# HUB_Sheet3.net
KiCad netlist of a schematic drawn in Altium Designer
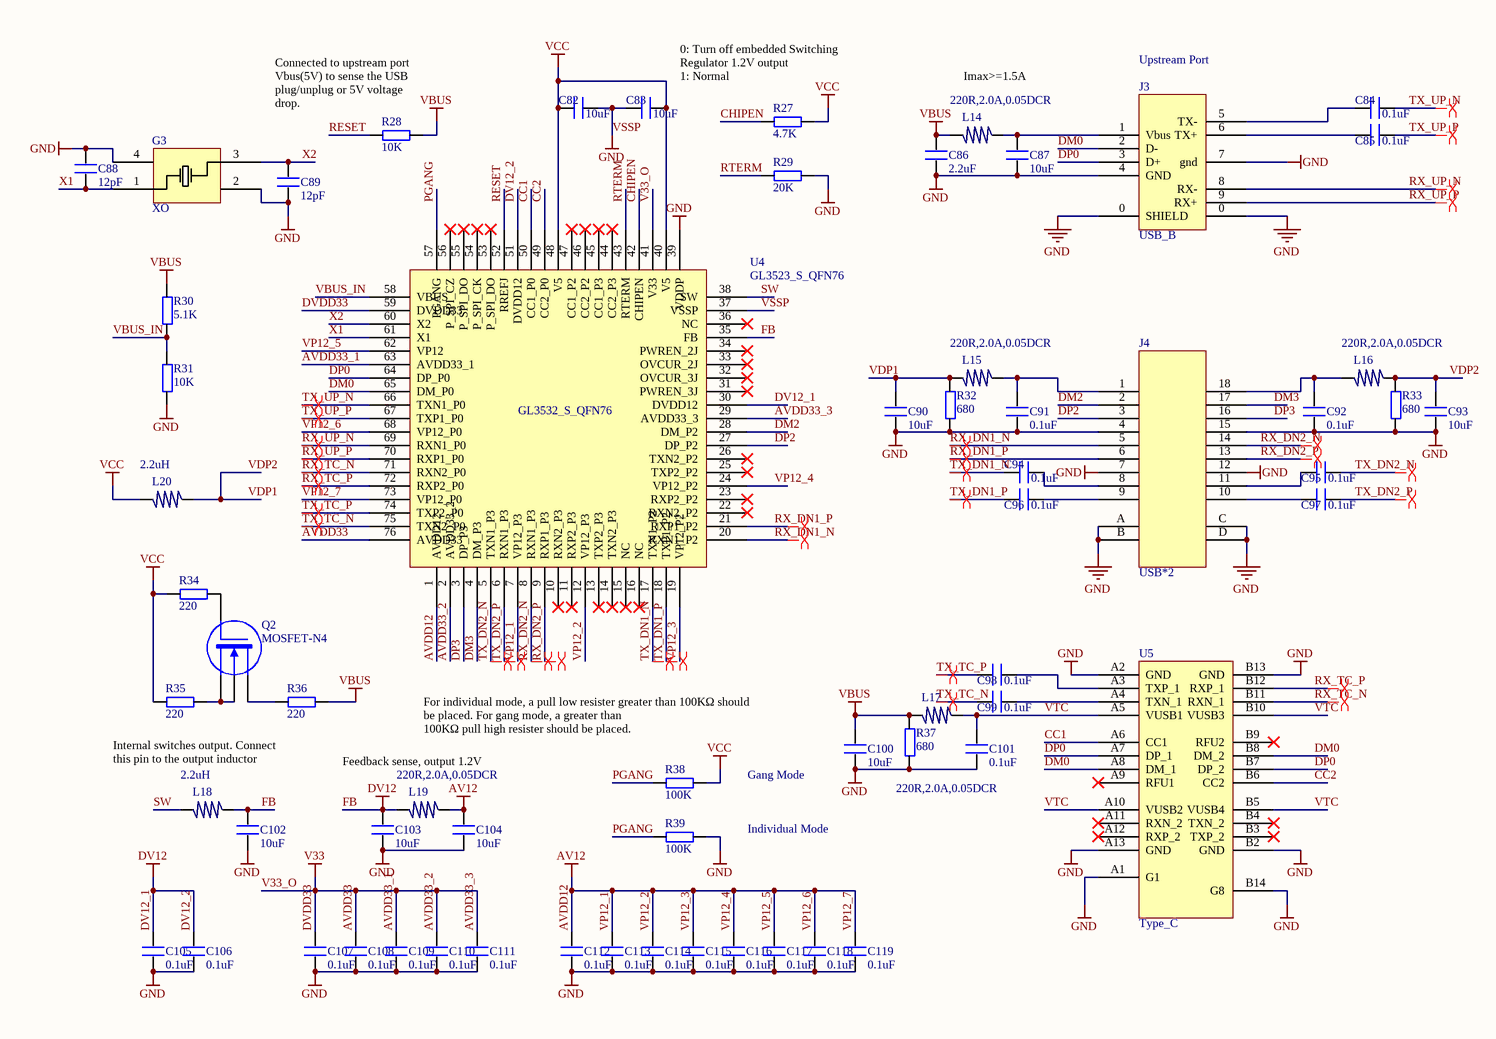
[diagram p0: HUB_Sheet3.SchDoc]

(export (version "E")
  (design (tool "Eeschema 10.0.6"))
  (components
    (comp (ref "C82") (value "10uF") (footprint "0603P") (libsource (lib "Explorer STM32F407封装库") (part "C")))
    (comp (ref "C83") (value "10uF") (footprint "0603P") (libsource (lib "Explorer STM32F407封装库") (part "C")))
    (comp (ref "C84")
      (value "0.1uF")
      (footprint "0603P")
      (libsource (lib "Explorer STM32F407封装库") (part "C"))
    )
    (comp (ref "C85")
      (value "0.1uF")
      (footprint "0603P")
      (libsource (lib "Explorer STM32F407封装库") (part "C"))
    )
    (comp (ref "C86")
      (value "2.2uF")
      (footprint "0603P")
      (libsource (lib "Explorer STM32F407封装库") (part "C"))
    )
    (comp (ref "C87") (value "10uF") (footprint "0603P") (libsource (lib "Explorer STM32F407封装库") (part "C")))
    (comp (ref "C88") (value "12pF") (footprint "0603P") (libsource (lib "Explorer STM32F407封装库") (part "C")))
    (comp (ref "C89") (value "12pF") (footprint "0603P") (libsource (lib "Explorer STM32F407封装库") (part "C")))
    (comp (ref "C90") (value "10uF") (footprint "0603P") (libsource (lib "Explorer STM32F407封装库") (part "C")))
    (comp (ref "C91")
      (value "0.1uF")
      (footprint "0603P")
      (libsource (lib "Explorer STM32F407封装库") (part "C"))
    )
    (comp (ref "C92")
      (value "0.1uF")
      (footprint "0603P")
      (libsource (lib "Explorer STM32F407封装库") (part "C"))
    )
    (comp (ref "C93") (value "10uF") (footprint "0603P") (libsource (lib "Explorer STM32F407封装库") (part "C")))
    (comp (ref "C94")
      (value "0.1uF")
      (footprint "0603P")
      (libsource (lib "Explorer STM32F407封装库") (part "C"))
    )
    (comp (ref "C95")
      (value "0.1uF")
      (footprint "0603P")
      (libsource (lib "Explorer STM32F407封装库") (part "C"))
    )
    (comp (ref "C96")
      (value "0.1uF")
      (footprint "0603P")
      (libsource (lib "Explorer STM32F407封装库") (part "C"))
    )
    (comp (ref "C97")
      (value "0.1uF")
      (footprint "0603P")
      (libsource (lib "Explorer STM32F407封装库") (part "C"))
    )
    (comp (ref "C98")
      (value "0.1uF")
      (footprint "0603P")
      (libsource (lib "Explorer STM32F407封装库") (part "C"))
    )
    (comp (ref "C99")
      (value "0.1uF")
      (footprint "0603P")
      (libsource (lib "Explorer STM32F407封装库") (part "C"))
    )
    (comp (ref "C100")
      (value "10uF")
      (footprint "0603P")
      (libsource (lib "Explorer STM32F407封装库") (part "C"))
    )
    (comp (ref "C101")
      (value "0.1uF")
      (footprint "0603P")
      (libsource (lib "Explorer STM32F407封装库") (part "C"))
    )
    (comp (ref "C102")
      (value "10uF")
      (footprint "0603P")
      (libsource (lib "Explorer STM32F407封装库") (part "C"))
    )
    (comp (ref "C103")
      (value "10uF")
      (footprint "0603P")
      (libsource (lib "Explorer STM32F407封装库") (part "C"))
    )
    (comp (ref "C104")
      (value "10uF")
      (footprint "0603P")
      (libsource (lib "Explorer STM32F407封装库") (part "C"))
    )
    (comp (ref "C105")
      (value "0.1uF")
      (footprint "0603P")
      (libsource (lib "Explorer STM32F407封装库") (part "C"))
    )
    (comp (ref "C106")
      (value "0.1uF")
      (footprint "0603P")
      (libsource (lib "Explorer STM32F407封装库") (part "C"))
    )
    (comp (ref "C107")
      (value "0.1uF")
      (footprint "0603P")
      (libsource (lib "Explorer STM32F407封装库") (part "C"))
    )
    (comp (ref "C108")
      (value "0.1uF")
      (footprint "0603P")
      (libsource (lib "Explorer STM32F407封装库") (part "C"))
    )
    (comp (ref "C109")
      (value "0.1uF")
      (footprint "0603P")
      (libsource (lib "Explorer STM32F407封装库") (part "C"))
    )
    (comp (ref "C110")
      (value "0.1uF")
      (footprint "0603P")
      (libsource (lib "Explorer STM32F407封装库") (part "C"))
    )
    (comp (ref "C111")
      (value "0.1uF")
      (footprint "0603P")
      (libsource (lib "Explorer STM32F407封装库") (part "C"))
    )
    (comp (ref "C112")
      (value "0.1uF")
      (footprint "0603P")
      (libsource (lib "Explorer STM32F407封装库") (part "C"))
    )
    (comp (ref "C113")
      (value "0.1uF")
      (footprint "0603P")
      (libsource (lib "Explorer STM32F407封装库") (part "C"))
    )
    (comp (ref "C114")
      (value "0.1uF")
      (footprint "0603P")
      (libsource (lib "Explorer STM32F407封装库") (part "C"))
    )
    (comp (ref "C115")
      (value "0.1uF")
      (footprint "0603P")
      (libsource (lib "Explorer STM32F407封装库") (part "C"))
    )
    (comp (ref "C116")
      (value "0.1uF")
      (footprint "0603P")
      (libsource (lib "Explorer STM32F407封装库") (part "C"))
    )
    (comp (ref "C117")
      (value "0.1uF")
      (footprint "0603P")
      (libsource (lib "Explorer STM32F407封装库") (part "C"))
    )
    (comp (ref "C118")
      (value "0.1uF")
      (footprint "0603P")
      (libsource (lib "Explorer STM32F407封装库") (part "C"))
    )
    (comp (ref "C119")
      (value "0.1uF")
      (footprint "0603P")
      (libsource (lib "Explorer STM32F407封装库") (part "C"))
    )
    (comp (ref "G3")
      (value "XO")
      (footprint "XTAL")
      (description "25M XO")
      (libsource (lib "HUB_GL3532") (part "XO"))
    )
    (comp (ref "J3")
      (value "USB_B")
      (footprint "USB3.0_TP")
      (description "USB3.0_B")
      (libsource (lib "HUB_GL3532") (part "USB_B"))
    )
    (comp (ref "J4")
      (value "USB*2")
      (footprint "USB3.0_Double_DIP")
      (libsource (lib "HUB_GL3532") (part "USB*2"))
    )
    (comp (ref "L14")
      (value "220R,2.0A,0.05DCR")
      (footprint "0603P")
      (libsource (lib "Explorer STM32F407封装库") (part "L"))
    )
    (comp (ref "L15")
      (value "220R,2.0A,0.05DCR")
      (footprint "0603P")
      (libsource (lib "Explorer STM32F407封装库") (part "L"))
    )
    (comp (ref "L16")
      (value "220R,2.0A,0.05DCR")
      (footprint "0603P")
      (libsource (lib "Explorer STM32F407封装库") (part "L"))
    )
    (comp (ref "L17")
      (value "220R,2.0A,0.05DCR")
      (footprint "0603P")
      (libsource (lib "Explorer STM32F407封装库") (part "L"))
    )
    (comp (ref "L18")
      (value "2.2uH")
      (footprint "0603P")
      (libsource (lib "Explorer STM32F407封装库") (part "L"))
    )
    (comp (ref "L19")
      (value "220R,2.0A,0.05DCR")
      (footprint "0603P")
      (libsource (lib "Explorer STM32F407封装库") (part "L"))
    )
    (comp (ref "L20")
      (value "2.2uH")
      (footprint "0603P")
      (libsource (lib "Explorer STM32F407封装库") (part "L"))
    )
    (comp (ref "Q2")
      (value "MOSFET-N4")
      (footprint "SOT-343_N")
      (description "N-Channel MOSFET, Externally Terminated Substrate")
      (fields (field (name "PUBLISHER") "Altium Limited"))
      (libsource (lib "Miscellaneous Devices") (part "MOSFET-N4"))
    )
    (comp (ref "R27") (value "4.7K") (footprint "0603P") (libsource (lib "Explorer STM32F407封装库") (part "R")))
    (comp (ref "R28") (value "10K") (footprint "0603P") (libsource (lib "Explorer STM32F407封装库") (part "R")))
    (comp (ref "R29") (value "20K") (footprint "0603P") (libsource (lib "Explorer STM32F407封装库") (part "R")))
    (comp (ref "R30") (value "5.1K") (footprint "0603P") (libsource (lib "Explorer STM32F407封装库") (part "R")))
    (comp (ref "R31") (value "10K") (footprint "0603P") (libsource (lib "Explorer STM32F407封装库") (part "R")))
    (comp (ref "R32") (value "680") (footprint "0603P") (libsource (lib "Explorer STM32F407封装库") (part "R")))
    (comp (ref "R33") (value "680") (footprint "0603P") (libsource (lib "Explorer STM32F407封装库") (part "R")))
    (comp (ref "R34") (value "220") (footprint "0603P") (libsource (lib "Explorer STM32F407封装库") (part "R")))
    (comp (ref "R35") (value "220") (footprint "0603P") (libsource (lib "Explorer STM32F407封装库") (part "R")))
    (comp (ref "R36") (value "220") (footprint "0603P") (libsource (lib "Explorer STM32F407封装库") (part "R")))
    (comp (ref "R37") (value "680") (footprint "0603P") (libsource (lib "Explorer STM32F407封装库") (part "R")))
    (comp (ref "R38") (value "100K") (footprint "0603P") (libsource (lib "Explorer STM32F407封装库") (part "R")))
    (comp (ref "R39") (value "100K") (footprint "0603P") (libsource (lib "Explorer STM32F407封装库") (part "R")))
    (comp (ref "U4")
      (value "GL3523_S_QFN76")
      (footprint "GL3523_QFN76")
      (libsource (lib "HUB_GL3532") (part "GL3523_S_QFN76"))
    )
    (comp (ref "U5") (value "Type_C") (libsource (lib "HUB_GL3532") (part "Type_C")))
  )
  (nets
    (net (code "1") (name "/CC1") (class "Default")
      (node (ref "U4") (pin "50") (pinfunction "CC1_P0_50") (pintype "passive"))
      (node (ref "U5") (pin "A6") (pinfunction "CC1_A6") (pintype "passive"))
    )
    (net (code "2") (name "/CC2") (class "Default")
      (node (ref "U4") (pin "49") (pinfunction "CC2_P0_49") (pintype "passive"))
      (node (ref "U5") (pin "B6") (pinfunction "CC2_B6") (pintype "passive"))
    )
    (net (code "3") (name "/CHIPEN") (class "Default")
      (node (ref "R27") (pin "1") (pintype "passive"))
      (node (ref "U4") (pin "42") (pinfunction "CHIPEN_42") (pintype "passive"))
    )
    (net (code "4") (name "/DM0") (class "Default")
      (node (ref "J3") (pin "2") (pinfunction "D-_2") (pintype "passive"))
      (node (ref "U4") (pin "65") (pinfunction "DM_P0_65") (pintype "passive"))
      (node (ref "U5") (pin "A8") (pinfunction "DM_1_A8") (pintype "passive"))
      (node (ref "U5") (pin "B8") (pinfunction "DM_2_B8") (pintype "passive"))
    )
    (net (code "5") (name "/DM2") (class "Default")
      (node (ref "J4") (pin "2") (pintype "passive"))
      (node (ref "U4") (pin "28") (pinfunction "DM_P2_28") (pintype "passive"))
    )
    (net (code "6") (name "/DM3") (class "Default")
      (node (ref "J4") (pin "17") (pintype "passive"))
      (node (ref "U4") (pin "4") (pinfunction "DM_P3_4") (pintype "passive"))
    )
    (net (code "7") (name "/DP0") (class "Default")
      (node (ref "J3") (pin "3") (pinfunction "D+_3") (pintype "passive"))
      (node (ref "U4") (pin "64") (pinfunction "DP_P0_64") (pintype "passive"))
      (node (ref "U5") (pin "A7") (pinfunction "DP_1_A7") (pintype "passive"))
      (node (ref "U5") (pin "B7") (pinfunction "DP_2_B7") (pintype "passive"))
    )
    (net (code "8") (name "/DP2") (class "Default")
      (node (ref "J4") (pin "3") (pintype "passive"))
      (node (ref "U4") (pin "27") (pinfunction "DP_P2_27") (pintype "passive"))
    )
    (net (code "9") (name "/DP3") (class "Default")
      (node (ref "J4") (pin "16") (pintype "passive"))
      (node (ref "U4") (pin "3") (pinfunction "DP_P3_3") (pintype "passive"))
    )
    (net (code "10") (name "/PGANG") (class "Default")
      (node (ref "R38") (pin "1") (pintype "passive"))
      (node (ref "R39") (pin "1") (pintype "passive"))
      (node (ref "U4") (pin "57") (pinfunction "PGANG_57") (pintype "passive"))
    )
    (net (code "11") (name "/RESET") (class "Default")
      (node (ref "R28") (pin "1") (pintype "passive"))
      (node (ref "U4") (pin "52") (pinfunction "RREFJ_52") (pintype "passive"))
    )
    (net (code "12") (name "/RTERM") (class "Default")
      (node (ref "R29") (pin "1") (pintype "passive"))
      (node (ref "U4") (pin "43") (pinfunction "RTERM_43") (pintype "passive"))
    )
    (net (code "13") (name "/RX_DN1_N") (class "Default")
      (node (ref "J4") (pin "5") (pintype "passive"))
      (node (ref "U4") (pin "20") (pinfunction "RXN1_P2_20") (pintype "passive"))
    )
    (net (code "14") (name "/RX_DN1_P") (class "Default")
      (node (ref "J4") (pin "6") (pintype "passive"))
      (node (ref "U4") (pin "21") (pinfunction "RXP1_P2_21") (pintype "passive"))
    )
    (net (code "15") (name "/RX_DN2_N") (class "Default")
      (node (ref "J4") (pin "14") (pintype "passive"))
      (node (ref "U4") (pin "8") (pinfunction "RXN1_P3_8") (pintype "passive"))
    )
    (net (code "16") (name "/RX_DN2_P") (class "Default")
      (node (ref "J4") (pin "13") (pintype "passive"))
      (node (ref "U4") (pin "9") (pinfunction "RXP1_P3_9") (pintype "passive"))
    )
    (net (code "17") (name "/RX_TC_N") (class "Default")
      (node (ref "U4") (pin "71") (pinfunction "RXN2_P0_71") (pintype "passive"))
      (node (ref "U5") (pin "B11") (pinfunction "RXN_1_B11") (pintype "passive"))
    )
    (net (code "18") (name "/RX_TC_P") (class "Default")
      (node (ref "U4") (pin "72") (pinfunction "RXP2_P0_72") (pintype "passive"))
      (node (ref "U5") (pin "B12") (pinfunction "RXP_1_B12") (pintype "passive"))
    )
    (net (code "19") (name "/RX_UP_N") (class "Default")
      (node (ref "J3") (pin "8") (pinfunction "RX-_8") (pintype "passive"))
      (node (ref "U4") (pin "69") (pinfunction "RXN1_P0_69") (pintype "passive"))
    )
    (net (code "20") (name "/RX_UP_P") (class "Default")
      (node (ref "J3") (pin "9") (pinfunction "RX+_9") (pintype "passive"))
      (node (ref "U4") (pin "70") (pinfunction "RXP1_P0_70") (pintype "passive"))
    )
    (net (code "21") (name "/SW") (class "Default")
      (node (ref "L18") (pin "2") (pintype "passive"))
      (node (ref "U4") (pin "38") (pinfunction "SW_38") (pintype "passive"))
    )
    (net (code "22") (name "/TX_DN1_N") (class "Default")
      (node (ref "C94") (pin "1") (pintype "passive"))
      (node (ref "U4") (pin "17") (pinfunction "TXN1_P2_17") (pintype "passive"))
    )
    (net (code "23") (name "/TX_DN1_P") (class "Default")
      (node (ref "C96") (pin "1") (pintype "passive"))
      (node (ref "U4") (pin "18") (pinfunction "TXP1_P2_18") (pintype "passive"))
    )
    (net (code "24") (name "/TX_DN2_N") (class "Default")
      (node (ref "C95") (pin "2") (pintype "passive"))
      (node (ref "U4") (pin "5") (pinfunction "TXN1_P3_5") (pintype "passive"))
    )
    (net (code "25") (name "/TX_DN2_P") (class "Default")
      (node (ref "C97") (pin "2") (pintype "passive"))
      (node (ref "U4") (pin "6") (pinfunction "RXN1_P3_6") (pintype "passive"))
    )
    (net (code "26") (name "/TX_TC_N") (class "Default")
      (node (ref "C99") (pin "1") (pintype "passive"))
      (node (ref "U4") (pin "75") (pinfunction "TXN2_P0_75") (pintype "passive"))
    )
    (net (code "27") (name "/TX_TC_P") (class "Default")
      (node (ref "C98") (pin "1") (pintype "passive"))
      (node (ref "U4") (pin "74") (pinfunction "TXP2_P0_74") (pintype "passive"))
    )
    (net (code "28") (name "/TX_UP_N") (class "Default")
      (node (ref "C84") (pin "2") (pintype "passive"))
      (node (ref "U4") (pin "66") (pinfunction "TXN1_P0_66") (pintype "passive"))
    )
    (net (code "29") (name "/TX_UP_P") (class "Default")
      (node (ref "C85") (pin "2") (pintype "passive"))
      (node (ref "U4") (pin "67") (pinfunction "TXP1_P0_67") (pintype "passive"))
    )
    (net (code "30") (name "/VBUS_IN") (class "Default")
      (node (ref "R30") (pin "1") (pintype "passive"))
      (node (ref "R31") (pin "2") (pintype "passive"))
      (node (ref "U4") (pin "58") (pinfunction "VBUS_58") (pintype "passive"))
    )
    (net (code "31") (name "/VDP1") (class "Default")
      (node (ref "C90") (pin "2") (pintype "passive"))
      (node (ref "C93") (pin "2") (pintype "passive"))
      (node (ref "L15") (pin "2") (pintype "passive"))
      (node (ref "L16") (pin "1") (pintype "passive"))
      (node (ref "L20") (pin "1") (pintype "passive"))
      (node (ref "R32") (pin "2") (pintype "passive"))
      (node (ref "R33") (pin "2") (pintype "passive"))
    )
    (net (code "32") (name "/VTC") (class "Default")
      (node (ref "C101") (pin "2") (pintype "passive"))
      (node (ref "L17") (pin "1") (pintype "passive"))
      (node (ref "U5") (pin "A10") (pinfunction "VUSB2_A10") (pintype "passive"))
      (node (ref "U5") (pin "A5") (pinfunction "VUSB1_A5") (pintype "passive"))
      (node (ref "U5") (pin "B10") (pinfunction "VUSB3_B10") (pintype "passive"))
      (node (ref "U5") (pin "B5") (pinfunction "VUSB4_B5") (pintype "passive"))
    )
    (net (code "33") (name "/X1") (class "Default")
      (node (ref "C88") (pin "1") (pintype "passive"))
      (node (ref "G3") (pin "1") (pintype "passive"))
      (node (ref "U4") (pin "61") (pinfunction "X1_61") (pintype "passive"))
    )
    (net (code "34") (name "/X2") (class "Default")
      (node (ref "C89") (pin "2") (pintype "passive"))
      (node (ref "G3") (pin "3") (pintype "passive"))
      (node (ref "U4") (pin "60") (pinfunction "X2_60") (pintype "passive"))
    )
    (net (code "35") (name "AV12") (class "Default")
      (node (ref "C104") (pin "2") (pintype "passive"))
      (node (ref "C112") (pin "2") (pintype "passive"))
      (node (ref "C113") (pin "2") (pintype "passive"))
      (node (ref "C114") (pin "2") (pintype "passive"))
      (node (ref "C115") (pin "2") (pintype "passive"))
      (node (ref "C116") (pin "2") (pintype "passive"))
      (node (ref "C117") (pin "2") (pintype "passive"))
      (node (ref "C118") (pin "2") (pintype "passive"))
      (node (ref "C119") (pin "2") (pintype "passive"))
      (node (ref "L19") (pin "1") (pintype "passive"))
      (node (ref "U4") (pin "1") (pinfunction "AVDD12_1") (pintype "passive"))
      (node (ref "U4") (pin "12") (pinfunction "VP12_P3_12") (pintype "passive"))
      (node (ref "U4") (pin "19") (pinfunction "VP12_P2_19") (pintype "passive"))
      (node (ref "U4") (pin "24") (pinfunction "VP12_P2_24") (pintype "passive"))
      (node (ref "U4") (pin "62") (pinfunction "VP12_62") (pintype "passive"))
      (node (ref "U4") (pin "68") (pinfunction "VP12_P0_68") (pintype "passive"))
      (node (ref "U4") (pin "7") (pinfunction "VP12_P3_7") (pintype "passive"))
      (node (ref "U4") (pin "73") (pinfunction "VP12_P0_73") (pintype "passive"))
    )
    (net (code "36") (name "DV12") (class "Default")
      (node (ref "C102") (pin "2") (pintype "passive"))
      (node (ref "C103") (pin "2") (pintype "passive"))
      (node (ref "C105") (pin "2") (pintype "passive"))
      (node (ref "C106") (pin "2") (pintype "passive"))
      (node (ref "L18") (pin "1") (pintype "passive"))
      (node (ref "L19") (pin "2") (pintype "passive"))
      (node (ref "U4") (pin "30") (pinfunction "DVDD12_30") (pintype "passive"))
      (node (ref "U4") (pin "35") (pinfunction "FB_35") (pintype "passive"))
      (node (ref "U4") (pin "51") (pinfunction "DVDD12_51") (pintype "passive"))
    )
    (net (code "37") (name "GND") (class "Default")
      (node (ref "C100") (pin "1") (pintype "passive"))
      (node (ref "C101") (pin "1") (pintype "passive"))
      (node (ref "C102") (pin "1") (pintype "passive"))
      (node (ref "C103") (pin "1") (pintype "passive"))
      (node (ref "C104") (pin "1") (pintype "passive"))
      (node (ref "C105") (pin "1") (pintype "passive"))
      (node (ref "C106") (pin "1") (pintype "passive"))
      (node (ref "C107") (pin "1") (pintype "passive"))
      (node (ref "C108") (pin "1") (pintype "passive"))
      (node (ref "C109") (pin "1") (pintype "passive"))
      (node (ref "C110") (pin "1") (pintype "passive"))
      (node (ref "C111") (pin "1") (pintype "passive"))
      (node (ref "C112") (pin "1") (pintype "passive"))
      (node (ref "C113") (pin "1") (pintype "passive"))
      (node (ref "C114") (pin "1") (pintype "passive"))
      (node (ref "C115") (pin "1") (pintype "passive"))
      (node (ref "C116") (pin "1") (pintype "passive"))
      (node (ref "C117") (pin "1") (pintype "passive"))
      (node (ref "C118") (pin "1") (pintype "passive"))
      (node (ref "C119") (pin "1") (pintype "passive"))
      (node (ref "C82") (pin "2") (pintype "passive"))
      (node (ref "C83") (pin "1") (pintype "passive"))
      (node (ref "C86") (pin "1") (pintype "passive"))
      (node (ref "C87") (pin "1") (pintype "passive"))
      (node (ref "C88") (pin "2") (pintype "passive"))
      (node (ref "C89") (pin "1") (pintype "passive"))
      (node (ref "C90") (pin "1") (pintype "passive"))
      (node (ref "C91") (pin "1") (pintype "passive"))
      (node (ref "C92") (pin "1") (pintype "passive"))
      (node (ref "C93") (pin "1") (pintype "passive"))
      (node (ref "G3") (pin "2") (pintype "passive"))
      (node (ref "G3") (pin "4") (pintype "passive"))
      (node (ref "J3") (pin "0") (pintype "passive"))
      (node (ref "J3") (pin "4") (pinfunction "GND_4") (pintype "passive"))
      (node (ref "J3") (pin "7") (pinfunction "gnd_7") (pintype "passive"))
      (node (ref "J4") (pin "12") (pintype "passive"))
      (node (ref "J4") (pin "15") (pintype "passive"))
      (node (ref "J4") (pin "4") (pintype "passive"))
      (node (ref "J4") (pin "7") (pintype "passive"))
      (node (ref "J4") (pin "A") (pintype "passive"))
      (node (ref "J4") (pin "B") (pintype "passive"))
      (node (ref "J4") (pin "C") (pintype "passive"))
      (node (ref "J4") (pin "D") (pintype "passive"))
      (node (ref "R29") (pin "2") (pintype "passive"))
      (node (ref "R31") (pin "1") (pintype "passive"))
      (node (ref "R32") (pin "1") (pintype "passive"))
      (node (ref "R33") (pin "1") (pintype "passive"))
      (node (ref "R37") (pin "1") (pintype "passive"))
      (node (ref "R39") (pin "2") (pintype "passive"))
      (node (ref "U4") (pin "37") (pinfunction "VSSP_37") (pintype "passive"))
      (node (ref "U4") (pin "39") (pinfunction "VDDP_39") (pintype "passive"))
      (node (ref "U5") (pin "A1") (pinfunction "G1_A1") (pintype "passive"))
      (node (ref "U5") (pin "A13") (pinfunction "GND_A13") (pintype "passive"))
      (node (ref "U5") (pin "A2") (pinfunction "GND_A2") (pintype "passive"))
      (node (ref "U5") (pin "B13") (pinfunction "GND_B13") (pintype "passive"))
      (node (ref "U5") (pin "B14") (pinfunction "G8_B14") (pintype "passive"))
      (node (ref "U5") (pin "B2") (pinfunction "GND_B2") (pintype "passive"))
    )
    (net (code "38") (name "Net-(C91-Pad2)") (class "Default")
      (node (ref "C91") (pin "2") (pintype "passive"))
      (node (ref "J4") (pin "1") (pintype "passive"))
      (node (ref "L15") (pin "1") (pintype "passive"))
    )
    (net (code "39") (name "Net-(C92-Pad2)") (class "Default")
      (node (ref "C92") (pin "2") (pintype "passive"))
      (node (ref "J4") (pin "18") (pintype "passive"))
      (node (ref "L16") (pin "2") (pintype "passive"))
    )
    (net (code "40") (name "Net-(C94-Pad2)") (class "Default")
      (node (ref "C94") (pin "2") (pintype "passive"))
      (node (ref "J4") (pin "8") (pintype "passive"))
    )
    (net (code "41") (name "Net-(C95-Pad1)") (class "Default")
      (node (ref "C95") (pin "1") (pintype "passive"))
      (node (ref "J4") (pin "11") (pintype "passive"))
    )
    (net (code "42") (name "Net-(C96-Pad2)") (class "Default")
      (node (ref "C96") (pin "2") (pintype "passive"))
      (node (ref "J4") (pin "9") (pintype "passive"))
    )
    (net (code "43") (name "Net-(C97-Pad1)") (class "Default")
      (node (ref "C97") (pin "1") (pintype "passive"))
      (node (ref "J4") (pin "10") (pintype "passive"))
    )
    (net (code "44") (name "Net-(J3-TX+)") (class "Default")
      (node (ref "C85") (pin "1") (pintype "passive"))
      (node (ref "J3") (pin "6") (pinfunction "TX+_6") (pintype "passive"))
    )
    (net (code "45") (name "Net-(J3-TX-)") (class "Default")
      (node (ref "C84") (pin "1") (pintype "passive"))
      (node (ref "J3") (pin "5") (pinfunction "TX-_5") (pintype "passive"))
    )
    (net (code "46") (name "Net-(J3-Vbus)") (class "Default")
      (node (ref "C87") (pin "2") (pintype "passive"))
      (node (ref "J3") (pin "1") (pinfunction "Vbus_1") (pintype "passive"))
      (node (ref "L14") (pin "1") (pintype "passive"))
    )
    (net (code "47") (name "Net-(Q2-D)") (class "Default")
      (node (ref "Q2") (pin "2") (pinfunction "D_2") (pintype "passive"))
      (node (ref "R36") (pin "1") (pintype "passive"))
    )
    (net (code "48") (name "Net-(Q2-G)") (class "Default")
      (node (ref "Q2") (pin "1") (pinfunction "G_1") (pintype "passive"))
      (node (ref "R34") (pin "2") (pintype "passive"))
    )
    (net (code "49") (name "Net-(Q2-S)") (class "Default")
      (node (ref "Q2") (pin "3") (pinfunction "U_3") (pintype "passive"))
      (node (ref "Q2") (pin "4") (pinfunction "S_4") (pintype "passive"))
      (node (ref "R35") (pin "2") (pintype "passive"))
    )
    (net (code "50") (name "Net-(U5-TXN_1)") (class "Default")
      (node (ref "C99") (pin "2") (pintype "passive"))
      (node (ref "U5") (pin "A4") (pinfunction "TXN_1_A4") (pintype "passive"))
    )
    (net (code "51") (name "Net-(U5-TXP_1)") (class "Default")
      (node (ref "C98") (pin "2") (pintype "passive"))
      (node (ref "U5") (pin "A3") (pinfunction "TXP_1_A3") (pintype "passive"))
    )
    (net (code "52") (name "V33") (class "Default")
      (node (ref "C107") (pin "2") (pintype "passive"))
      (node (ref "C108") (pin "2") (pintype "passive"))
      (node (ref "C109") (pin "2") (pintype "passive"))
      (node (ref "C110") (pin "2") (pintype "passive"))
      (node (ref "C111") (pin "2") (pintype "passive"))
      (node (ref "U4") (pin "2") (pinfunction "AVDD33_2_2") (pintype "passive"))
      (node (ref "U4") (pin "29") (pinfunction "AVDD33_3_29") (pintype "passive"))
      (node (ref "U4") (pin "41") (pinfunction "V33_41") (pintype "passive"))
      (node (ref "U4") (pin "59") (pinfunction "DVDD33_59") (pintype "passive"))
      (node (ref "U4") (pin "63") (pinfunction "AVDD33_1_63") (pintype "passive"))
      (node (ref "U4") (pin "76") (pinfunction "AVDD33_76") (pintype "passive"))
    )
    (net (code "53") (name "VBUS") (class "Default")
      (node (ref "C100") (pin "2") (pintype "passive"))
      (node (ref "C86") (pin "2") (pintype "passive"))
      (node (ref "L14") (pin "2") (pintype "passive"))
      (node (ref "L17") (pin "2") (pintype "passive"))
      (node (ref "R28") (pin "2") (pintype "passive"))
      (node (ref "R30") (pin "2") (pintype "passive"))
      (node (ref "R36") (pin "2") (pintype "passive"))
      (node (ref "R37") (pin "2") (pintype "passive"))
    )
    (net (code "54") (name "VCC") (class "Default")
      (node (ref "C82") (pin "1") (pintype "passive"))
      (node (ref "C83") (pin "2") (pintype "passive"))
      (node (ref "L20") (pin "2") (pintype "passive"))
      (node (ref "R27") (pin "2") (pintype "passive"))
      (node (ref "R34") (pin "1") (pintype "passive"))
      (node (ref "R35") (pin "1") (pintype "passive"))
      (node (ref "R38") (pin "2") (pintype "passive"))
      (node (ref "U4") (pin "40") (pinfunction "V5_40") (pintype "passive"))
      (node (ref "U4") (pin "48") (pinfunction "V5_48") (pintype "passive"))
    )
    (net (code "55") (name "unconnected-(U4-CC1_P2-Pad47)") (class "Default")
      (node (ref "U4") (pin "47") (pinfunction "CC1_P2_47") (pintype "passive+no_connect"))
    )
    (net (code "56") (name "unconnected-(U4-CC1_P3-Pad45)") (class "Default")
      (node (ref "U4") (pin "45") (pinfunction "CC1_P3_45") (pintype "passive+no_connect"))
    )
    (net (code "57") (name "unconnected-(U4-CC2_P2-Pad46)") (class "Default")
      (node (ref "U4") (pin "46") (pinfunction "CC2_P2_46") (pintype "passive+no_connect"))
    )
    (net (code "58") (name "unconnected-(U4-CC2_P3-Pad44)") (class "Default")
      (node (ref "U4") (pin "44") (pinfunction "CC2_P3_44") (pintype "passive+no_connect"))
    )
    (net (code "59") (name "unconnected-(U4-NC-Pad15)") (class "Default")
      (node (ref "U4") (pin "15") (pinfunction "NC_15") (pintype "passive+no_connect"))
    )
    (net (code "60") (name "unconnected-(U4-NC-Pad16)") (class "Default")
      (node (ref "U4") (pin "16") (pinfunction "NC_16") (pintype "passive+no_connect"))
    )
    (net (code "61") (name "unconnected-(U4-NC-Pad36)") (class "Default")
      (node (ref "U4") (pin "36") (pinfunction "NC_36") (pintype "passive+no_connect"))
    )
    (net (code "62") (name "unconnected-(U4-OVCUR_2J-Pad33)") (class "Default")
      (node (ref "U4") (pin "33") (pinfunction "OVCUR_2J_33") (pintype "passive+no_connect"))
    )
    (net (code "63") (name "unconnected-(U4-OVCUR_3J-Pad32)") (class "Default")
      (node (ref "U4") (pin "32") (pinfunction "OVCUR_3J_32") (pintype "passive+no_connect"))
    )
    (net (code "64") (name "unconnected-(U4-PWREN_2J-Pad34)") (class "Default")
      (node (ref "U4") (pin "34") (pinfunction "PWREN_2J_34") (pintype "passive+no_connect"))
    )
    (net (code "65") (name "unconnected-(U4-PWREN_3J-Pad31)") (class "Default")
      (node (ref "U4") (pin "31") (pinfunction "PWREN_3J_31") (pintype "passive+no_connect"))
    )
    (net (code "66") (name "unconnected-(U4-P_SPI_CK-Pad54)") (class "Default")
      (node (ref "U4") (pin "54") (pinfunction "P_SPI_CK_54") (pintype "passive+no_connect"))
    )
    (net (code "67") (name "unconnected-(U4-P_SPI_CZ-Pad56)") (class "Default")
      (node (ref "U4") (pin "56") (pinfunction "P_SPI_CZ_56") (pintype "passive+no_connect"))
    )
    (net (code "68") (name "unconnected-(U4-P_SPI_DO-Pad53)") (class "Default")
      (node (ref "U4") (pin "53") (pinfunction "P_SPI_DO_53") (pintype "passive+no_connect"))
    )
    (net (code "69") (name "unconnected-(U4-P_SPI_DO-Pad55)") (class "Default")
      (node (ref "U4") (pin "55") (pinfunction "P_SPI_DO_55") (pintype "passive+no_connect"))
    )
    (net (code "70") (name "unconnected-(U4-RXN2_P2-Pad22)") (class "Default")
      (node (ref "U4") (pin "22") (pinfunction "RXN2_P2_22") (pintype "passive+no_connect"))
    )
    (net (code "71") (name "unconnected-(U4-RXN2_P3-Pad10)") (class "Default")
      (node (ref "U4") (pin "10") (pinfunction "RXN2_P3_10") (pintype "passive+no_connect"))
    )
    (net (code "72") (name "unconnected-(U4-RXP2_P2-Pad23)") (class "Default")
      (node (ref "U4") (pin "23") (pinfunction "RXP2_P2_23") (pintype "passive+no_connect"))
    )
    (net (code "73") (name "unconnected-(U4-RXP2_P3-Pad11)") (class "Default")
      (node (ref "U4") (pin "11") (pinfunction "RXP2_P3_11") (pintype "passive+no_connect"))
    )
    (net (code "74") (name "unconnected-(U4-TXN2_P2-Pad26)") (class "Default")
      (node (ref "U4") (pin "26") (pinfunction "TXN2_P2_26") (pintype "passive+no_connect"))
    )
    (net (code "75") (name "unconnected-(U4-TXN2_P3-Pad14)") (class "Default")
      (node (ref "U4") (pin "14") (pinfunction "TXN2_P3_14") (pintype "passive+no_connect"))
    )
    (net (code "76") (name "unconnected-(U4-TXP2_P2-Pad25)") (class "Default")
      (node (ref "U4") (pin "25") (pinfunction "TXP2_P2_25") (pintype "passive+no_connect"))
    )
    (net (code "77") (name "unconnected-(U4-TXP2_P3-Pad13)") (class "Default")
      (node (ref "U4") (pin "13") (pinfunction "TXP2_P3_13") (pintype "passive+no_connect"))
    )
    (net (code "78") (name "unconnected-(U5-RFU1-PadA9)") (class "Default")
      (node (ref "U5") (pin "A9") (pinfunction "RFU1_A9") (pintype "passive+no_connect"))
    )
    (net (code "79") (name "unconnected-(U5-RFU2-PadB9)") (class "Default")
      (node (ref "U5") (pin "B9") (pinfunction "RFU2_B9") (pintype "passive+no_connect"))
    )
    (net (code "80") (name "unconnected-(U5-RXN_2-PadA11)") (class "Default")
      (node (ref "U5") (pin "A11") (pinfunction "RXN_2_A11") (pintype "passive+no_connect"))
    )
    (net (code "81") (name "unconnected-(U5-RXP_2-PadA12)") (class "Default")
      (node (ref "U5") (pin "A12") (pinfunction "RXP_2_A12") (pintype "passive+no_connect"))
    )
    (net (code "82") (name "unconnected-(U5-TXN_2-PadB4)") (class "Default")
      (node (ref "U5") (pin "B4") (pinfunction "TXN_2_B4") (pintype "passive+no_connect"))
    )
    (net (code "83") (name "unconnected-(U5-TXP_2-PadB3)") (class "Default")
      (node (ref "U5") (pin "B3") (pinfunction "TXP_2_B3") (pintype "passive+no_connect"))
    )
  )
)
